# watch_tubes_final.net
KiCad netlist of a schematic drawn in EAGLE
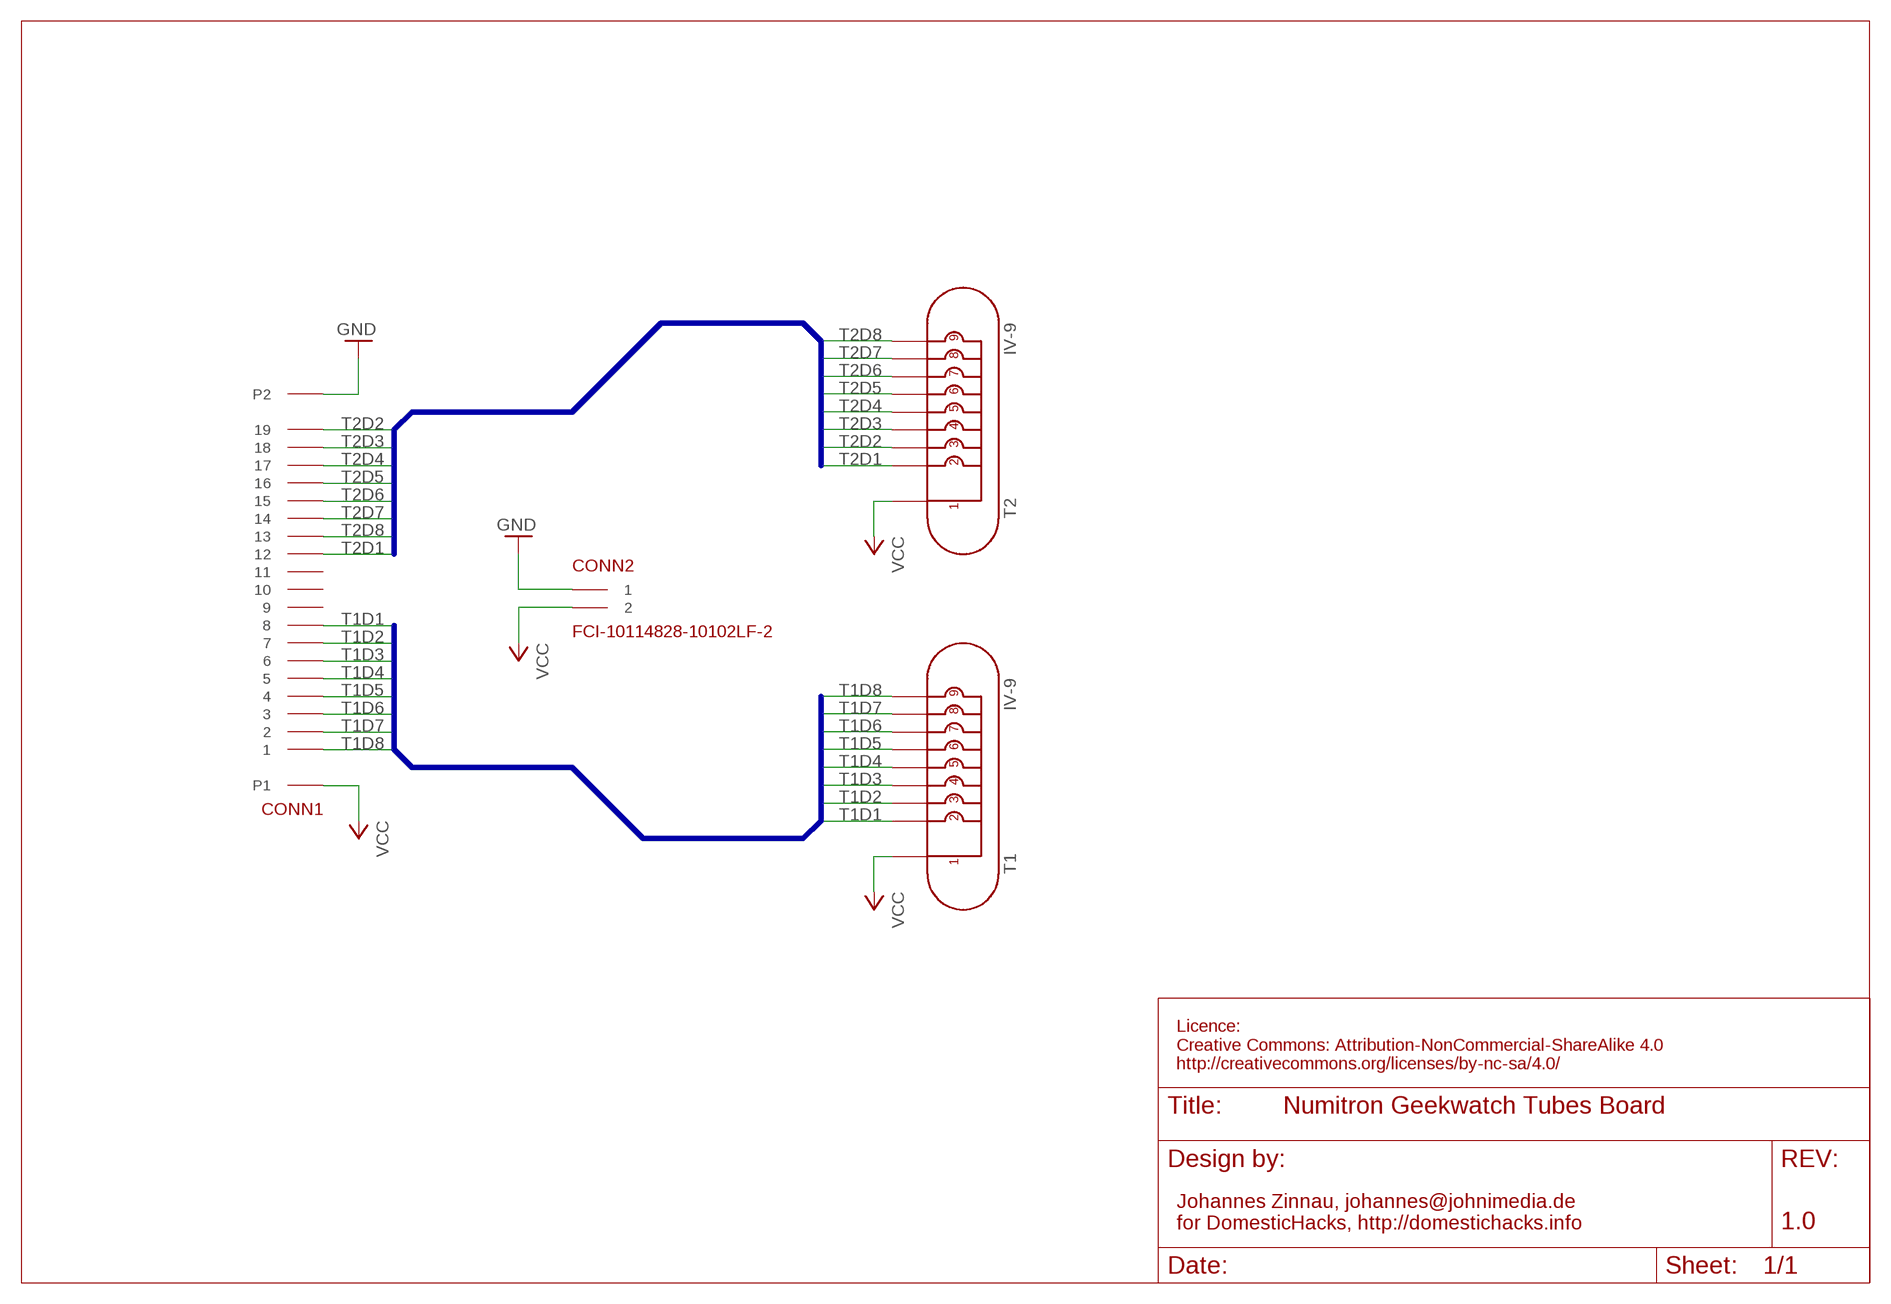
[diagram p0: schematic, sheet 1]

(export (version "E")
  (design (tool "Eeschema 10.0.6"))
  (components
    (comp (ref "CONN1")
      (value "PCBMOUNT-20SECOND")
      (footprint "eagle-import:PCBMOUNT-VERTICAL-20-2")
      (libsource (lib "eagle-import") (part "PCBMOUNT-20SECOND"))
    )
    (comp (ref "CONN2")
      (value "FCI-10114828-10102LF-2")
      (footprint "eagle-import:FCI-10114828-10102LF-2")
      (libsource (lib "eagle-import") (part "FCI-10114828-10102LF-2"))
    )
    (comp (ref "T1")
      (value "IV-9")
      (footprint "eagle-import:IV-9")
      (libsource (lib "eagle-import") (part "IV-9"))
    )
    (comp (ref "T2")
      (value "IV-9")
      (footprint "eagle-import:IV-9")
      (libsource (lib "eagle-import") (part "IV-9"))
    )
  )
  (nets
    (net (code "1") (name "/T1D1") (class "Default")
      (node (ref "CONN1") (pin "8") (pinfunction "8_8") (pintype "bidirectional"))
      (node (ref "T1") (pin "2") (pinfunction "2_2") (pintype "bidirectional"))
    )
    (net (code "2") (name "/T1D2") (class "Default")
      (node (ref "CONN1") (pin "7") (pinfunction "7_7") (pintype "bidirectional"))
      (node (ref "T1") (pin "3") (pinfunction "3_3") (pintype "bidirectional"))
    )
    (net (code "3") (name "/T1D3") (class "Default")
      (node (ref "CONN1") (pin "6") (pinfunction "6_6") (pintype "bidirectional"))
      (node (ref "T1") (pin "4") (pinfunction "4_4") (pintype "bidirectional"))
    )
    (net (code "4") (name "/T1D4") (class "Default")
      (node (ref "CONN1") (pin "5") (pinfunction "5_5") (pintype "bidirectional"))
      (node (ref "T1") (pin "5") (pinfunction "5_5") (pintype "bidirectional"))
    )
    (net (code "5") (name "/T1D5") (class "Default")
      (node (ref "CONN1") (pin "4") (pinfunction "4_4") (pintype "bidirectional"))
      (node (ref "T1") (pin "6") (pinfunction "6_6") (pintype "bidirectional"))
    )
    (net (code "6") (name "/T1D6") (class "Default")
      (node (ref "CONN1") (pin "3") (pinfunction "3_3") (pintype "bidirectional"))
      (node (ref "T1") (pin "7") (pinfunction "7_7") (pintype "bidirectional"))
    )
    (net (code "7") (name "/T1D7") (class "Default")
      (node (ref "CONN1") (pin "2") (pinfunction "2_2") (pintype "bidirectional"))
      (node (ref "T1") (pin "8") (pinfunction "8_8") (pintype "bidirectional"))
    )
    (net (code "8") (name "/T1D8") (class "Default")
      (node (ref "CONN1") (pin "1") (pinfunction "1_1") (pintype "bidirectional"))
      (node (ref "T1") (pin "9") (pinfunction "9_9") (pintype "bidirectional"))
    )
    (net (code "9") (name "/T2D1") (class "Default")
      (node (ref "CONN1") (pin "12") (pinfunction "12_12") (pintype "bidirectional"))
      (node (ref "T2") (pin "2") (pinfunction "2_2") (pintype "bidirectional"))
    )
    (net (code "10") (name "/T2D2") (class "Default")
      (node (ref "CONN1") (pin "19") (pinfunction "19_19") (pintype "bidirectional"))
      (node (ref "T2") (pin "3") (pinfunction "3_3") (pintype "bidirectional"))
    )
    (net (code "11") (name "/T2D3") (class "Default")
      (node (ref "CONN1") (pin "18") (pinfunction "18_18") (pintype "bidirectional"))
      (node (ref "T2") (pin "4") (pinfunction "4_4") (pintype "bidirectional"))
    )
    (net (code "12") (name "/T2D4") (class "Default")
      (node (ref "CONN1") (pin "17") (pinfunction "17_17") (pintype "bidirectional"))
      (node (ref "T2") (pin "5") (pinfunction "5_5") (pintype "bidirectional"))
    )
    (net (code "13") (name "/T2D5") (class "Default")
      (node (ref "CONN1") (pin "16") (pinfunction "16_16") (pintype "bidirectional"))
      (node (ref "T2") (pin "6") (pinfunction "6_6") (pintype "bidirectional"))
    )
    (net (code "14") (name "/T2D6") (class "Default")
      (node (ref "CONN1") (pin "15") (pinfunction "15_15") (pintype "bidirectional"))
      (node (ref "T2") (pin "7") (pinfunction "7_7") (pintype "bidirectional"))
    )
    (net (code "15") (name "/T2D7") (class "Default")
      (node (ref "CONN1") (pin "14") (pinfunction "14_14") (pintype "bidirectional"))
      (node (ref "T2") (pin "8") (pinfunction "8_8") (pintype "bidirectional"))
    )
    (net (code "16") (name "/T2D8") (class "Default")
      (node (ref "CONN1") (pin "13") (pinfunction "13_13") (pintype "bidirectional"))
      (node (ref "T2") (pin "9") (pinfunction "9_9") (pintype "bidirectional"))
    )
    (net (code "17") (name "GND") (class "Default")
      (node (ref "CONN1") (pin "P2") (pinfunction "P2_P2") (pintype "bidirectional"))
      (node (ref "CONN2") (pin "1") (pinfunction "1_1") (pintype "bidirectional"))
    )
    (net (code "18") (name "VCC") (class "Default")
      (node (ref "CONN1") (pin "P1") (pinfunction "P1_P1") (pintype "bidirectional"))
      (node (ref "CONN2") (pin "2") (pinfunction "2_2") (pintype "bidirectional"))
      (node (ref "T1") (pin "1") (pinfunction "1_1") (pintype "bidirectional"))
      (node (ref "T2") (pin "1") (pinfunction "1_1") (pintype "bidirectional"))
    )
    (net (code "19") (name "unconnected-(CONN1-Pad9)") (class "Default")
      (node (ref "CONN1") (pin "9") (pinfunction "9_9") (pintype "bidirectional"))
    )
    (net (code "20") (name "unconnected-(CONN1-Pad10)") (class "Default")
      (node (ref "CONN1") (pin "10") (pinfunction "10_10") (pintype "bidirectional"))
    )
    (net (code "21") (name "unconnected-(CONN1-Pad11)") (class "Default")
      (node (ref "CONN1") (pin "11") (pinfunction "11_11") (pintype "bidirectional"))
    )
  )
)
